# IMU_MAG.net
KiCad netlist of a schematic drawn in Altium Designer
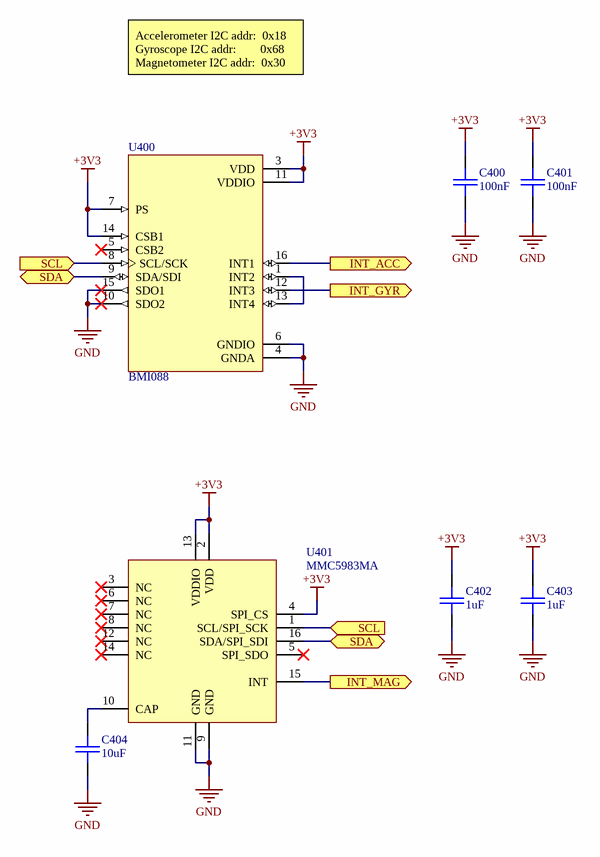
[diagram p0: IMU_MAG.SchDoc]

(export (version "E")
  (design (tool "Eeschema 10.0.6"))
  (components
    (comp (ref "C400")
      (value "100nF")
      (footprint "0603_CAP")
      (libsource (lib "Moonlight_Components") (part "Capacitor"))
    )
    (comp (ref "C401")
      (value "100nF")
      (footprint "0603_CAP")
      (libsource (lib "Moonlight_Components") (part "Capacitor"))
    )
    (comp (ref "C402")
      (value "1uF")
      (footprint "0603_CAP")
      (libsource (lib "Moonlight_Components") (part "Capacitor"))
    )
    (comp (ref "C403")
      (value "1uF")
      (footprint "0603_CAP")
      (libsource (lib "Moonlight_Components") (part "Capacitor"))
    )
    (comp (ref "C404")
      (value "10uF")
      (footprint "0603_CAP")
      (libsource (lib "Moonlight_Components") (part "Capacitor"))
    )
    (comp (ref "U400")
      (value "BMI088")
      (footprint "BMI088")
      (description "Digikey part no. 828-1082-1-ND")
      (fields (field (name "MF") "Bosch Sensortec"))
      (libsource (lib "Moonlight_Components") (part "BMI088"))
    )
    (comp (ref "U401")
      (value "MMC5983MA")
      (footprint "MMC5983MA")
      (description "3 axis magnetometer")
      (libsource (lib "Moonlight_Components") (part "MMC5983MA"))
    )
  )
  (nets
    (net (code "1") (name "+3V3") (class "Default")
      (node (ref "C400") (pin "1") (pinfunction "1_1") (pintype "passive"))
      (node (ref "C401") (pin "1") (pinfunction "1_1") (pintype "passive"))
      (node (ref "C402") (pin "1") (pinfunction "1_1") (pintype "passive"))
      (node (ref "C403") (pin "1") (pinfunction "1_1") (pintype "passive"))
      (node (ref "U400") (pin "11") (pinfunction "VDDIO_11") (pintype "power_in"))
      (node (ref "U400") (pin "14") (pinfunction "CSB1_14") (pintype "input"))
      (node (ref "U400") (pin "3") (pinfunction "VDD_3") (pintype "power_in"))
      (node (ref "U400") (pin "7") (pinfunction "PS_7") (pintype "input"))
      (node (ref "U401") (pin "13") (pinfunction "VDDIO_13") (pintype "passive"))
      (node (ref "U401") (pin "2") (pinfunction "VDD_2") (pintype "passive"))
      (node (ref "U401") (pin "4") (pinfunction "SPI_CS_4") (pintype "passive"))
    )
    (net (code "2") (name "/INT_ACC") (class "Default")
      (node (ref "U400") (pin "16") (pinfunction "INT1_16") (pintype "bidirectional"))
    )
    (net (code "3") (name "/INT_GYR") (class "Default")
      (node (ref "U400") (pin "12") (pinfunction "INT3_12") (pintype "bidirectional"))
    )
    (net (code "4") (name "/INT_MAG") (class "Default")
      (node (ref "U401") (pin "15") (pinfunction "INT_15") (pintype "passive"))
    )
    (net (code "5") (name "/SCL") (class "Default")
      (node (ref "U400") (pin "8") (pinfunction "SCL/SCK_8") (pintype "input"))
      (node (ref "U401") (pin "1") (pinfunction "SCL/SPI_SCK_1") (pintype "passive"))
    )
    (net (code "6") (name "/SDA") (class "Default")
      (node (ref "U400") (pin "9") (pinfunction "SDA/SDI_9") (pintype "bidirectional"))
      (node (ref "U401") (pin "16") (pinfunction "SDA/SPI_SDI_16") (pintype "passive"))
    )
    (net (code "7") (name "GND") (class "Default")
      (node (ref "C400") (pin "2") (pinfunction "2_2") (pintype "passive"))
      (node (ref "C401") (pin "2") (pinfunction "2_2") (pintype "passive"))
      (node (ref "C402") (pin "2") (pinfunction "2_2") (pintype "passive"))
      (node (ref "C403") (pin "2") (pinfunction "2_2") (pintype "passive"))
      (node (ref "C404") (pin "2") (pinfunction "2_2") (pintype "passive"))
      (node (ref "U400") (pin "10") (pinfunction "SDO2_10") (pintype "output"))
      (node (ref "U400") (pin "15") (pinfunction "SDO1_15") (pintype "output"))
      (node (ref "U400") (pin "4") (pinfunction "GNDA_4") (pintype "power_in"))
      (node (ref "U400") (pin "6") (pinfunction "GNDIO_6") (pintype "power_in"))
      (node (ref "U401") (pin "11") (pinfunction "GND_11") (pintype "passive"))
      (node (ref "U401") (pin "9") (pinfunction "GND_9") (pintype "passive"))
    )
    (net (code "8") (name "Net-(U400-INT2)") (class "Default")
      (node (ref "U400") (pin "1") (pinfunction "INT2_1") (pintype "bidirectional"))
      (node (ref "U400") (pin "13") (pinfunction "INT4_13") (pintype "bidirectional"))
    )
    (net (code "9") (name "Net-(U401-CAP)") (class "Default")
      (node (ref "C404") (pin "1") (pinfunction "1_1") (pintype "passive"))
      (node (ref "U401") (pin "10") (pinfunction "CAP_10") (pintype "passive"))
    )
    (net (code "10") (name "unconnected-(U400-CSB2-Pad5)") (class "Default")
      (node (ref "U400") (pin "5") (pinfunction "CSB2_5") (pintype "input+no_connect"))
    )
    (net (code "11") (name "unconnected-(U401-NC-Pad3)") (class "Default")
      (node (ref "U401") (pin "3") (pinfunction "NC_3") (pintype "passive+no_connect"))
    )
    (net (code "12") (name "unconnected-(U401-NC-Pad6)") (class "Default")
      (node (ref "U401") (pin "6") (pinfunction "NC_6") (pintype "passive+no_connect"))
    )
    (net (code "13") (name "unconnected-(U401-NC-Pad7)") (class "Default")
      (node (ref "U401") (pin "7") (pinfunction "NC_7") (pintype "passive+no_connect"))
    )
    (net (code "14") (name "unconnected-(U401-NC-Pad8)") (class "Default")
      (node (ref "U401") (pin "8") (pinfunction "NC_8") (pintype "passive+no_connect"))
    )
    (net (code "15") (name "unconnected-(U401-NC-Pad12)") (class "Default")
      (node (ref "U401") (pin "12") (pinfunction "NC_12") (pintype "passive+no_connect"))
    )
    (net (code "16") (name "unconnected-(U401-NC-Pad14)") (class "Default")
      (node (ref "U401") (pin "14") (pinfunction "NC_14") (pintype "passive+no_connect"))
    )
    (net (code "17") (name "unconnected-(U401-SPI_SDO-Pad5)") (class "Default")
      (node (ref "U401") (pin "5") (pinfunction "SPI_SDO_5") (pintype "passive+no_connect"))
    )
  )
)
